# adc.net
KiCad netlist of a schematic drawn in Altium Designer
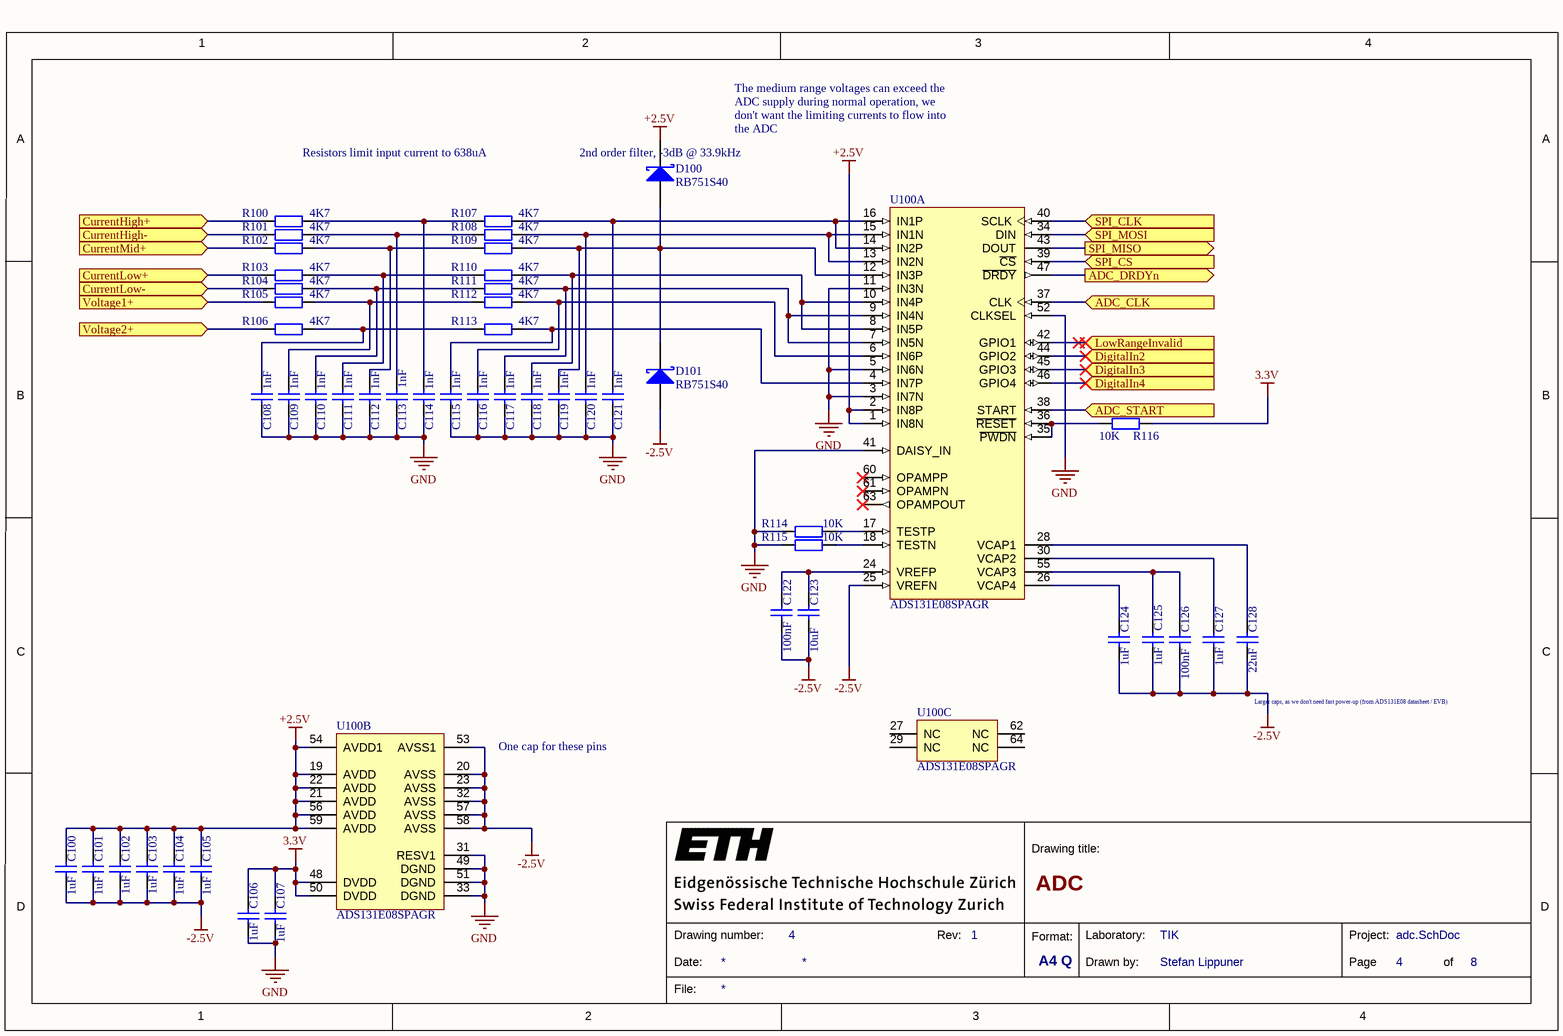
[diagram p0: adc.SchDoc]

(export (version "E")
  (design (tool "Eeschema 10.0.6"))
  (components
    (comp (ref "C100")
      (value "1uF")
      (footprint "CAPC0402(1005)60_L")
      (description "CAP 1uF 16V ±20% 0402 (1005 Metric) Thickness 0.6mm SMD")
      (fields (field (name "TOLERANCE") "Â±20%"))
      (libsource (lib "Altium Content Vault") (part "CMP-1034-02120"))
    )
    (comp (ref "C101")
      (value "1uF")
      (footprint "CAPC0402(1005)60_L")
      (description "CAP 1uF 16V ±20% 0402 (1005 Metric) Thickness 0.6mm SMD")
      (fields (field (name "TOLERANCE") "Â±20%"))
      (libsource (lib "Altium Content Vault") (part "CMP-1034-02120"))
    )
    (comp (ref "C102")
      (value "1uF")
      (footprint "CAPC0402(1005)60_L")
      (description "CAP 1uF 16V ±20% 0402 (1005 Metric) Thickness 0.6mm SMD")
      (fields (field (name "TOLERANCE") "Â±20%"))
      (libsource (lib "Altium Content Vault") (part "CMP-1034-02120"))
    )
    (comp (ref "C103")
      (value "1uF")
      (footprint "CAPC0402(1005)60_L")
      (description "CAP 1uF 16V ±20% 0402 (1005 Metric) Thickness 0.6mm SMD")
      (fields (field (name "TOLERANCE") "Â±20%"))
      (libsource (lib "Altium Content Vault") (part "CMP-1034-02120"))
    )
    (comp (ref "C104")
      (value "1uF")
      (footprint "CAPC0402(1005)60_L")
      (description "CAP 1uF 16V ±20% 0402 (1005 Metric) Thickness 0.6mm SMD")
      (fields (field (name "TOLERANCE") "Â±20%"))
      (libsource (lib "Altium Content Vault") (part "CMP-1034-02120"))
    )
    (comp (ref "C105")
      (value "1uF")
      (footprint "CAPC0402(1005)60_L")
      (description "CAP 1uF 16V ±20% 0402 (1005 Metric) Thickness 0.6mm SMD")
      (fields (field (name "TOLERANCE") "Â±20%"))
      (libsource (lib "Altium Content Vault") (part "CMP-1034-02120"))
    )
    (comp (ref "C106")
      (value "1uF")
      (footprint "CAPC0402(1005)60_L")
      (description "CAP 1uF 16V ±20% 0402 (1005 Metric) Thickness 0.6mm SMD")
      (fields (field (name "TOLERANCE") "Â±20%"))
      (libsource (lib "Altium Content Vault") (part "CMP-1034-02120"))
    )
    (comp (ref "C107")
      (value "1uF")
      (footprint "CAPC0402(1005)60_L")
      (description "CAP 1uF 16V ±20% 0402 (1005 Metric) Thickness 0.6mm SMD")
      (fields (field (name "TOLERANCE") "Â±20%"))
      (libsource (lib "Altium Content Vault") (part "CMP-1034-02120"))
    )
    (comp (ref "C108")
      (value "1nF")
      (footprint "CAPC0402(1005)60_L")
      (description "CAP 1nF 50V ±5% 0402 (1005 Metric) Thickness 0.6mm SMD")
      (fields (field (name "TOLERANCE") "Â±5%"))
      (libsource (lib "Altium Content Vault") (part "CAP"))
    )
    (comp (ref "C109")
      (value "1nF")
      (footprint "CAPC0402(1005)60_L")
      (description "CAP 1nF 50V ±5% 0402 (1005 Metric) Thickness 0.6mm SMD")
      (fields (field (name "TOLERANCE") "Â±5%"))
      (libsource (lib "Altium Content Vault") (part "CAP"))
    )
    (comp (ref "C110")
      (value "1nF")
      (footprint "CAPC0402(1005)60_L")
      (description "CAP 1nF 50V ±5% 0402 (1005 Metric) Thickness 0.6mm SMD")
      (fields (field (name "TOLERANCE") "Â±5%"))
      (libsource (lib "Altium Content Vault") (part "CAP"))
    )
    (comp (ref "C111")
      (value "1nF")
      (footprint "CAPC0402(1005)60_L")
      (description "CAP 1nF 50V ±5% 0402 (1005 Metric) Thickness 0.6mm SMD")
      (fields (field (name "TOLERANCE") "Â±5%"))
      (libsource (lib "Altium Content Vault") (part "CAP"))
    )
    (comp (ref "C112")
      (value "1nF")
      (footprint "CAPC0402(1005)60_L")
      (description "CAP 1nF 50V ±5% 0402 (1005 Metric) Thickness 0.6mm SMD")
      (fields (field (name "TOLERANCE") "Â±5%"))
      (libsource (lib "Altium Content Vault") (part "CAP"))
    )
    (comp (ref "C113")
      (value "1nF")
      (footprint "CAPC0402(1005)60_L")
      (description "CAP 1nF 50V ±5% 0402 (1005 Metric) Thickness 0.6mm SMD")
      (fields (field (name "TOLERANCE") "Â±5%"))
      (libsource (lib "Altium Content Vault") (part "CAP"))
    )
    (comp (ref "C114")
      (value "1nF")
      (footprint "CAPC0402(1005)60_L")
      (description "CAP 1nF 50V ±5% 0402 (1005 Metric) Thickness 0.6mm SMD")
      (fields (field (name "TOLERANCE") "Â±5%"))
      (libsource (lib "Altium Content Vault") (part "CAP"))
    )
    (comp (ref "C115")
      (value "1nF")
      (footprint "CAPC0402(1005)60_L")
      (description "CAP 1nF 50V ±5% 0402 (1005 Metric) Thickness 0.6mm SMD")
      (fields (field (name "TOLERANCE") "Â±5%"))
      (libsource (lib "Altium Content Vault") (part "CAP"))
    )
    (comp (ref "C116")
      (value "1nF")
      (footprint "CAPC0402(1005)60_L")
      (description "CAP 1nF 50V ±5% 0402 (1005 Metric) Thickness 0.6mm SMD")
      (fields (field (name "TOLERANCE") "Â±5%"))
      (libsource (lib "Altium Content Vault") (part "CAP"))
    )
    (comp (ref "C117")
      (value "1nF")
      (footprint "CAPC0402(1005)60_L")
      (description "CAP 1nF 50V ±5% 0402 (1005 Metric) Thickness 0.6mm SMD")
      (fields (field (name "TOLERANCE") "Â±5%"))
      (libsource (lib "Altium Content Vault") (part "CAP"))
    )
    (comp (ref "C118")
      (value "1nF")
      (footprint "CAPC0402(1005)60_L")
      (description "CAP 1nF 50V ±5% 0402 (1005 Metric) Thickness 0.6mm SMD")
      (fields (field (name "TOLERANCE") "Â±5%"))
      (libsource (lib "Altium Content Vault") (part "CAP"))
    )
    (comp (ref "C119")
      (value "1nF")
      (footprint "CAPC0402(1005)60_L")
      (description "CAP 1nF 50V ±5% 0402 (1005 Metric) Thickness 0.6mm SMD")
      (fields (field (name "TOLERANCE") "Â±5%"))
      (libsource (lib "Altium Content Vault") (part "CAP"))
    )
    (comp (ref "C120")
      (value "1nF")
      (footprint "CAPC0402(1005)60_L")
      (description "CAP 1nF 50V ±5% 0402 (1005 Metric) Thickness 0.6mm SMD")
      (fields (field (name "TOLERANCE") "Â±5%"))
      (libsource (lib "Altium Content Vault") (part "CAP"))
    )
    (comp (ref "C121")
      (value "1nF")
      (footprint "CAPC0402(1005)60_L")
      (description "CAP 1nF 50V ±5% 0402 (1005 Metric) Thickness 0.6mm SMD")
      (fields (field (name "TOLERANCE") "Â±5%"))
      (libsource (lib "Altium Content Vault") (part "CAP"))
    )
    (comp (ref "C122")
      (value "100nF")
      (footprint "CAPC0402(1005)60_L")
      (description "CAP 100nF 16V -20% to +80% 0402 (1005 Metric) Thickness 0.6mm SMD")
      (fields (field (name "TOLERANCE") "-20% to +80%"))
      (libsource (lib "Altium Content Vault") (part "CMP-1034-02071-1"))
    )
    (comp (ref "C123")
      (value "10uF")
      (footprint "CAPC0603(1608)100_L")
      (description "CAP 10uF 10V ±20% 0603 (1608 Metric) Thickness 1mm SMD")
      (fields (field (name "TOLERANCE") "Â±20%"))
      (libsource (lib "Altium Content Vault") (part "CMP-1035-02800-1"))
    )
    (comp (ref "C124")
      (value "1uF")
      (footprint "CAPC0402(1005)60_L")
      (description "CAP 1uF 16V ±20% 0402 (1005 Metric) Thickness 0.6mm SMD")
      (fields (field (name "TOLERANCE") "Â±20%"))
      (libsource (lib "Altium Content Vault") (part "CMP-1034-02120"))
    )
    (comp (ref "C125")
      (value "1uF")
      (footprint "CAPC0402(1005)60_L")
      (description "CAP 1uF 16V ±20% 0402 (1005 Metric) Thickness 0.6mm SMD")
      (fields (field (name "TOLERANCE") "Â±20%"))
      (libsource (lib "Altium Content Vault") (part "CMP-1034-02120"))
    )
    (comp (ref "C126")
      (value "100nF")
      (footprint "CAPC0402(1005)60_L")
      (description "CAP 100nF 16V -20% to +80% 0402 (1005 Metric) Thickness 0.6mm SMD")
      (fields (field (name "TOLERANCE") "-20% to +80%"))
      (libsource (lib "Altium Content Vault") (part "CMP-1034-02071-1"))
    )
    (comp (ref "C127")
      (value "1uF")
      (footprint "CAPC0402(1005)60_L")
      (description "CAP 1uF 16V ±20% 0402 (1005 Metric) Thickness 0.6mm SMD")
      (fields (field (name "TOLERANCE") "Â±20%"))
      (libsource (lib "Altium Content Vault") (part "CMP-1034-02120"))
    )
    (comp (ref "C128")
      (value "22uF")
      (footprint "CAPC0805(2012)145_L")
      (description "CAP 22uF 6.3V ±10% 0805 (2012 Metric) Thickness 1.45mm SMD")
      (fields (field (name "TOLERANCE") "Â±10%"))
      (libsource (lib "Altium Content Vault") (part "CAP"))
    )
    (comp (ref "D100")
      (value "RB751S40")
      (footprint "ONSC-SOD-523-2-502-01_V")
      (description "DIODE SCHOTTKY 40V 30MA SOD523F")
      (fields (field (name "MANUFACTURER") "Fairchild Semiconductor"))
      (libsource (lib "ETHZ Vault") (part "CMP-00225-2"))
    )
    (comp (ref "D101")
      (value "RB751S40")
      (footprint "ONSC-SOD-523-2-502-01_V")
      (description "DIODE SCHOTTKY 40V 30MA SOD523F")
      (fields (field (name "MANUFACTURER") "Fairchild Semiconductor"))
      (libsource (lib "ETHZ Vault") (part "Diode Schottky"))
    )
    (comp (ref "R100")
      (value "4K7")
      (footprint "RESC0402(1005)_L")
      (description "4K7 0.063W 1% 0402 (1005 Metric)  SMD")
      (fields (field (name "POWER") "0.063 W") (field (name "TOLERANCE") "1 %"))
      (libsource (lib "Altium Content Vault") (part "RES"))
    )
    (comp (ref "R101")
      (value "4K7")
      (footprint "RESC0402(1005)_L")
      (description "4K7 0.063W 1% 0402 (1005 Metric)  SMD")
      (fields (field (name "POWER") "0.063 W") (field (name "TOLERANCE") "1 %"))
      (libsource (lib "Altium Content Vault") (part "RES"))
    )
    (comp (ref "R102")
      (value "4K7")
      (footprint "RESC0402(1005)_L")
      (description "4K7 0.063W 1% 0402 (1005 Metric)  SMD")
      (fields (field (name "POWER") "0.063 W") (field (name "TOLERANCE") "1 %"))
      (libsource (lib "Altium Content Vault") (part "RES"))
    )
    (comp (ref "R103")
      (value "4K7")
      (footprint "RESC0402(1005)_L")
      (description "4K7 0.063W 1% 0402 (1005 Metric)  SMD")
      (fields (field (name "POWER") "0.063 W") (field (name "TOLERANCE") "1 %"))
      (libsource (lib "Altium Content Vault") (part "RES"))
    )
    (comp (ref "R104")
      (value "4K7")
      (footprint "RESC0402(1005)_L")
      (description "4K7 0.063W 1% 0402 (1005 Metric)  SMD")
      (fields (field (name "POWER") "0.063 W") (field (name "TOLERANCE") "1 %"))
      (libsource (lib "Altium Content Vault") (part "RES"))
    )
    (comp (ref "R105")
      (value "4K7")
      (footprint "RESC0402(1005)_L")
      (description "4K7 0.063W 1% 0402 (1005 Metric)  SMD")
      (fields (field (name "POWER") "0.063 W") (field (name "TOLERANCE") "1 %"))
      (libsource (lib "Altium Content Vault") (part "RES"))
    )
    (comp (ref "R106")
      (value "4K7")
      (footprint "RESC0402(1005)_L")
      (description "4K7 0.063W 1% 0402 (1005 Metric)  SMD")
      (fields (field (name "POWER") "0.063 W") (field (name "TOLERANCE") "1 %"))
      (libsource (lib "Altium Content Vault") (part "RES"))
    )
    (comp (ref "R107")
      (value "4K7")
      (footprint "RESC0402(1005)_L")
      (description "4K7 0.063W 1% 0402 (1005 Metric)  SMD")
      (fields (field (name "POWER") "0.063 W") (field (name "TOLERANCE") "1 %"))
      (libsource (lib "Altium Content Vault") (part "RES"))
    )
    (comp (ref "R108")
      (value "4K7")
      (footprint "RESC0402(1005)_L")
      (description "4K7 0.063W 1% 0402 (1005 Metric)  SMD")
      (fields (field (name "POWER") "0.063 W") (field (name "TOLERANCE") "1 %"))
      (libsource (lib "Altium Content Vault") (part "RES"))
    )
    (comp (ref "R109")
      (value "4K7")
      (footprint "RESC0402(1005)_L")
      (description "4K7 0.063W 1% 0402 (1005 Metric)  SMD")
      (fields (field (name "POWER") "0.063 W") (field (name "TOLERANCE") "1 %"))
      (libsource (lib "Altium Content Vault") (part "RES"))
    )
    (comp (ref "R110")
      (value "4K7")
      (footprint "RESC0402(1005)_L")
      (description "4K7 0.063W 1% 0402 (1005 Metric)  SMD")
      (fields (field (name "POWER") "0.063 W") (field (name "TOLERANCE") "1 %"))
      (libsource (lib "Altium Content Vault") (part "RES"))
    )
    (comp (ref "R111")
      (value "4K7")
      (footprint "RESC0402(1005)_L")
      (description "4K7 0.063W 1% 0402 (1005 Metric)  SMD")
      (fields (field (name "POWER") "0.063 W") (field (name "TOLERANCE") "1 %"))
      (libsource (lib "Altium Content Vault") (part "RES"))
    )
    (comp (ref "R112")
      (value "4K7")
      (footprint "RESC0402(1005)_L")
      (description "4K7 0.063W 1% 0402 (1005 Metric)  SMD")
      (fields (field (name "POWER") "0.063 W") (field (name "TOLERANCE") "1 %"))
      (libsource (lib "Altium Content Vault") (part "RES"))
    )
    (comp (ref "R113")
      (value "4K7")
      (footprint "RESC0402(1005)_L")
      (description "4K7 0.063W 1% 0402 (1005 Metric)  SMD")
      (fields (field (name "POWER") "0.063 W") (field (name "TOLERANCE") "1 %"))
      (libsource (lib "Altium Content Vault") (part "RES"))
    )
    (comp (ref "R114")
      (value "10K")
      (footprint "RESC0402(1005)_L")
      (description "10K 0.063W 1% 0402 (1005 Metric)  SMD")
      (fields (field (name "TOLERANCE") "1 %") (field (name "POWER") "0.063 W"))
      (libsource (lib "Altium Content Vault") (part "CMP-1011-00623-1"))
    )
    (comp (ref "R115")
      (value "10K")
      (footprint "RESC0402(1005)_L")
      (description "10K 0.063W 1% 0402 (1005 Metric)  SMD")
      (fields (field (name "TOLERANCE") "1 %") (field (name "POWER") "0.063 W"))
      (libsource (lib "Altium Content Vault") (part "CMP-1011-00623-1"))
    )
    (comp (ref "R116")
      (value "10K")
      (footprint "RESC0402(1005)_L")
      (description "10K 0.063W 1% 0402 (1005 Metric)  SMD")
      (fields (field (name "TOLERANCE") "1 %") (field (name "POWER") "0.063 W"))
      (libsource (lib "Altium Content Vault") (part "RES"))
    )
    (comp (ref "U100")
      (value "ADS131E08SPAGR")
      (footprint "QFP50P1000X1000X120_HS-64L")
      (description "Analog to Digital Converters - ADC 8-Channel, 24-Bit, AFE")
      (fields (field (name "MANUFACTURER") "Texas Instruments"))
      (libsource (lib "ETHZ Vault") (part "ADS131E08S"))
    )
  )
  (nets
    (net (code "1") (name "+2.5V") (class "Default")
      (node (ref "C100") (pin "2") (pinfunction "2_2") (pintype "passive"))
      (node (ref "C101") (pin "2") (pinfunction "2_2") (pintype "passive"))
      (node (ref "C102") (pin "2") (pinfunction "2_2") (pintype "passive"))
      (node (ref "C103") (pin "2") (pinfunction "2_2") (pintype "passive"))
      (node (ref "C104") (pin "2") (pinfunction "2_2") (pintype "passive"))
      (node (ref "C105") (pin "2") (pinfunction "2_2") (pintype "passive"))
      (node (ref "D100") (pin "1") (pinfunction "K_1") (pintype "passive"))
      (node (ref "U100") (pin "1") (pinfunction "IN8N_1") (pintype "input"))
      (node (ref "U100") (pin "19") (pinfunction "AVDD_19") (pintype "power_in"))
      (node (ref "U100") (pin "2") (pinfunction "IN8P_2") (pintype "input"))
      (node (ref "U100") (pin "21") (pinfunction "AVDD_21") (pintype "power_in"))
      (node (ref "U100") (pin "22") (pinfunction "AVDD_22") (pintype "power_in"))
      (node (ref "U100") (pin "54") (pinfunction "AVDD1_54") (pintype "power_in"))
      (node (ref "U100") (pin "56") (pinfunction "AVDD_56") (pintype "power_in"))
      (node (ref "U100") (pin "59") (pinfunction "AVDD_59") (pintype "power_in"))
    )
    (net (code "2") (name "-2.5V") (class "Default")
      (node (ref "C100") (pin "1") (pinfunction "1_1") (pintype "passive"))
      (node (ref "C101") (pin "1") (pinfunction "1_1") (pintype "passive"))
      (node (ref "C102") (pin "1") (pinfunction "1_1") (pintype "passive"))
      (node (ref "C103") (pin "1") (pinfunction "1_1") (pintype "passive"))
      (node (ref "C104") (pin "1") (pinfunction "1_1") (pintype "passive"))
      (node (ref "C105") (pin "1") (pinfunction "1_1") (pintype "passive"))
      (node (ref "C122") (pin "1") (pinfunction "1_1") (pintype "passive"))
      (node (ref "C123") (pin "1") (pinfunction "1_1") (pintype "passive"))
      (node (ref "C124") (pin "1") (pinfunction "1_1") (pintype "passive"))
      (node (ref "C125") (pin "1") (pinfunction "1_1") (pintype "passive"))
      (node (ref "C126") (pin "1") (pinfunction "1_1") (pintype "passive"))
      (node (ref "C127") (pin "1") (pinfunction "1_1") (pintype "passive"))
      (node (ref "C128") (pin "1") (pinfunction "1_1") (pintype "passive"))
      (node (ref "D101") (pin "2") (pinfunction "A_2") (pintype "passive"))
      (node (ref "U100") (pin "20") (pinfunction "AVSS_20") (pintype "power_in"))
      (node (ref "U100") (pin "23") (pinfunction "AVSS_23") (pintype "power_in"))
      (node (ref "U100") (pin "25") (pinfunction "VREFN_25") (pintype "input"))
      (node (ref "U100") (pin "32") (pinfunction "AVSS_32") (pintype "power_in"))
      (node (ref "U100") (pin "53") (pinfunction "AVSS1_53") (pintype "power_in"))
      (node (ref "U100") (pin "57") (pinfunction "AVSS_57") (pintype "power_in"))
      (node (ref "U100") (pin "58") (pinfunction "AVSS_58") (pintype "power_in"))
    )
    (net (code "3") (name "/ADC_CLK") (class "Default")
      (node (ref "U100") (pin "37") (pinfunction "CLK_37") (pintype "input"))
    )
    (net (code "4") (name "/ADC_DRDYn") (class "Default")
      (node (ref "U100") (pin "47") (pinfunction "~{DRDY}_47") (pintype "output"))
    )
    (net (code "5") (name "/ADC_START") (class "Default")
      (node (ref "U100") (pin "38") (pinfunction "START_38") (pintype "input"))
    )
    (net (code "6") (name "/CurrentHigh+") (class "Default")
      (node (ref "R100") (pin "2") (pinfunction "2_2") (pintype "passive"))
    )
    (net (code "7") (name "/CurrentHigh-") (class "Default")
      (node (ref "R101") (pin "2") (pinfunction "2_2") (pintype "passive"))
    )
    (net (code "8") (name "/CurrentLow+") (class "Default")
      (node (ref "R103") (pin "2") (pinfunction "2_2") (pintype "passive"))
    )
    (net (code "9") (name "/CurrentLow-") (class "Default")
      (node (ref "R104") (pin "2") (pinfunction "2_2") (pintype "passive"))
    )
    (net (code "10") (name "/CurrentMid+") (class "Default")
      (node (ref "R102") (pin "2") (pinfunction "2_2") (pintype "passive"))
    )
    (net (code "11") (name "/DigitalIn2") (class "Default")
      (node (ref "U100") (pin "44") (pinfunction "GPIO2_44") (pintype "bidirectional+no_connect"))
    )
    (net (code "12") (name "/DigitalIn3") (class "Default")
      (node (ref "U100") (pin "45") (pinfunction "GPIO3_45") (pintype "bidirectional+no_connect"))
    )
    (net (code "13") (name "/DigitalIn4") (class "Default")
      (node (ref "U100") (pin "46") (pinfunction "GPIO4_46") (pintype "bidirectional+no_connect"))
    )
    (net (code "14") (name "/LowRangeInvalid") (class "Default")
      (node (ref "U100") (pin "42") (pinfunction "GPIO1_42") (pintype "bidirectional+no_connect"))
    )
    (net (code "15") (name "/SPI_CLK") (class "Default")
      (node (ref "U100") (pin "40") (pinfunction "SCLK_40") (pintype "input"))
    )
    (net (code "16") (name "/SPI_CS") (class "Default")
      (node (ref "U100") (pin "39") (pinfunction "~{CS}_39") (pintype "input"))
    )
    (net (code "17") (name "/SPI_MISO") (class "Default")
      (node (ref "U100") (pin "43") (pinfunction "DOUT_43") (pintype "tri_state"))
    )
    (net (code "18") (name "/SPI_MOSI") (class "Default")
      (node (ref "U100") (pin "34") (pinfunction "DIN_34") (pintype "input"))
    )
    (net (code "19") (name "/Voltage1+") (class "Default")
      (node (ref "R105") (pin "2") (pinfunction "2_2") (pintype "passive"))
    )
    (net (code "20") (name "/Voltage2+") (class "Default")
      (node (ref "R106") (pin "2") (pinfunction "2_2") (pintype "passive"))
    )
    (net (code "21") (name "3.3V") (class "Default")
      (node (ref "C106") (pin "2") (pinfunction "2_2") (pintype "passive"))
      (node (ref "C107") (pin "2") (pinfunction "2_2") (pintype "passive"))
      (node (ref "R116") (pin "1") (pinfunction "1_1") (pintype "passive"))
      (node (ref "U100") (pin "48") (pinfunction "DVDD_48") (pintype "power_in"))
      (node (ref "U100") (pin "50") (pinfunction "DVDD_50") (pintype "power_in"))
    )
    (net (code "22") (name "GND") (class "Default")
      (node (ref "C106") (pin "1") (pinfunction "1_1") (pintype "passive"))
      (node (ref "C107") (pin "1") (pinfunction "1_1") (pintype "passive"))
      (node (ref "C108") (pin "1") (pinfunction "1_1") (pintype "passive"))
      (node (ref "C109") (pin "1") (pinfunction "1_1") (pintype "passive"))
      (node (ref "C110") (pin "1") (pinfunction "1_1") (pintype "passive"))
      (node (ref "C111") (pin "1") (pinfunction "1_1") (pintype "passive"))
      (node (ref "C112") (pin "1") (pinfunction "1_1") (pintype "passive"))
      (node (ref "C113") (pin "1") (pinfunction "1_1") (pintype "passive"))
      (node (ref "C114") (pin "1") (pinfunction "1_1") (pintype "passive"))
      (node (ref "C115") (pin "1") (pinfunction "1_1") (pintype "passive"))
      (node (ref "C116") (pin "1") (pinfunction "1_1") (pintype "passive"))
      (node (ref "C117") (pin "1") (pinfunction "1_1") (pintype "passive"))
      (node (ref "C118") (pin "1") (pinfunction "1_1") (pintype "passive"))
      (node (ref "C119") (pin "1") (pinfunction "1_1") (pintype "passive"))
      (node (ref "C120") (pin "1") (pinfunction "1_1") (pintype "passive"))
      (node (ref "C121") (pin "1") (pinfunction "1_1") (pintype "passive"))
      (node (ref "R114") (pin "1") (pinfunction "1_1") (pintype "passive"))
      (node (ref "R115") (pin "1") (pinfunction "1_1") (pintype "passive"))
      (node (ref "U100") (pin "11") (pinfunction "IN3N_11") (pintype "input"))
      (node (ref "U100") (pin "3") (pinfunction "IN7N_3") (pintype "input"))
      (node (ref "U100") (pin "31") (pinfunction "RESV1_31") (pintype "power_in"))
      (node (ref "U100") (pin "33") (pinfunction "DGND_33") (pintype "power_in"))
      (node (ref "U100") (pin "41") (pinfunction "DAISY_IN_41") (pintype "input"))
      (node (ref "U100") (pin "49") (pinfunction "DGND_49") (pintype "power_in"))
      (node (ref "U100") (pin "5") (pinfunction "IN6N_5") (pintype "input"))
      (node (ref "U100") (pin "51") (pinfunction "DGND_51") (pintype "power_in"))
      (node (ref "U100") (pin "52") (pinfunction "CLKSEL_52") (pintype "input"))
    )
    (net (code "23") (name "Net-(C108-Pad2)") (class "Default")
      (node (ref "C108") (pin "2") (pinfunction "2_2") (pintype "passive"))
      (node (ref "R106") (pin "1") (pinfunction "1_1") (pintype "passive"))
      (node (ref "R113") (pin "2") (pinfunction "2_2") (pintype "passive"))
    )
    (net (code "24") (name "Net-(C109-Pad2)") (class "Default")
      (node (ref "C109") (pin "2") (pinfunction "2_2") (pintype "passive"))
      (node (ref "R105") (pin "1") (pinfunction "1_1") (pintype "passive"))
      (node (ref "R112") (pin "2") (pinfunction "2_2") (pintype "passive"))
    )
    (net (code "25") (name "Net-(C110-Pad2)") (class "Default")
      (node (ref "C110") (pin "2") (pinfunction "2_2") (pintype "passive"))
      (node (ref "R104") (pin "1") (pinfunction "1_1") (pintype "passive"))
      (node (ref "R111") (pin "2") (pinfunction "2_2") (pintype "passive"))
    )
    (net (code "26") (name "Net-(C111-Pad2)") (class "Default")
      (node (ref "C111") (pin "2") (pinfunction "2_2") (pintype "passive"))
      (node (ref "R103") (pin "1") (pinfunction "1_1") (pintype "passive"))
      (node (ref "R110") (pin "2") (pinfunction "2_2") (pintype "passive"))
    )
    (net (code "27") (name "Net-(C112-Pad2)") (class "Default")
      (node (ref "C112") (pin "2") (pinfunction "2_2") (pintype "passive"))
      (node (ref "R102") (pin "1") (pinfunction "1_1") (pintype "passive"))
      (node (ref "R109") (pin "2") (pinfunction "2_2") (pintype "passive"))
    )
    (net (code "28") (name "Net-(C113-Pad2)") (class "Default")
      (node (ref "C113") (pin "2") (pinfunction "2_2") (pintype "passive"))
      (node (ref "R101") (pin "1") (pinfunction "1_1") (pintype "passive"))
      (node (ref "R108") (pin "2") (pinfunction "2_2") (pintype "passive"))
    )
    (net (code "29") (name "Net-(C114-Pad2)") (class "Default")
      (node (ref "C114") (pin "2") (pinfunction "2_2") (pintype "passive"))
      (node (ref "R100") (pin "1") (pinfunction "1_1") (pintype "passive"))
      (node (ref "R107") (pin "2") (pinfunction "2_2") (pintype "passive"))
    )
    (net (code "30") (name "Net-(D100-A)") (class "Default")
      (node (ref "C119") (pin "2") (pinfunction "2_2") (pintype "passive"))
      (node (ref "D100") (pin "2") (pinfunction "A_2") (pintype "passive"))
      (node (ref "D101") (pin "1") (pinfunction "K_1") (pintype "passive"))
      (node (ref "R109") (pin "1") (pinfunction "1_1") (pintype "passive"))
      (node (ref "U100") (pin "12") (pinfunction "IN3P_12") (pintype "input"))
    )
    (net (code "31") (name "Net-(U100A-IN1N)") (class "Default")
      (node (ref "C120") (pin "2") (pinfunction "2_2") (pintype "passive"))
      (node (ref "R108") (pin "1") (pinfunction "1_1") (pintype "passive"))
      (node (ref "U100") (pin "13") (pinfunction "IN2N_13") (pintype "input"))
      (node (ref "U100") (pin "15") (pinfunction "IN1N_15") (pintype "input"))
    )
    (net (code "32") (name "Net-(U100A-IN1P)") (class "Default")
      (node (ref "C121") (pin "2") (pinfunction "2_2") (pintype "passive"))
      (node (ref "R107") (pin "1") (pinfunction "1_1") (pintype "passive"))
      (node (ref "U100") (pin "14") (pinfunction "IN2P_14") (pintype "input"))
      (node (ref "U100") (pin "16") (pinfunction "IN1P_16") (pintype "input"))
    )
    (net (code "33") (name "Net-(U100A-IN4N)") (class "Default")
      (node (ref "C117") (pin "2") (pinfunction "2_2") (pintype "passive"))
      (node (ref "R111") (pin "1") (pinfunction "1_1") (pintype "passive"))
      (node (ref "U100") (pin "7") (pinfunction "IN5N_7") (pintype "input"))
      (node (ref "U100") (pin "9") (pinfunction "IN4N_9") (pintype "input"))
    )
    (net (code "34") (name "Net-(U100A-IN4P)") (class "Default")
      (node (ref "C118") (pin "2") (pinfunction "2_2") (pintype "passive"))
      (node (ref "R110") (pin "1") (pinfunction "1_1") (pintype "passive"))
      (node (ref "U100") (pin "10") (pinfunction "IN4P_10") (pintype "input"))
      (node (ref "U100") (pin "8") (pinfunction "IN5P_8") (pintype "input"))
    )
    (net (code "35") (name "Net-(U100A-IN6P)") (class "Default")
      (node (ref "C116") (pin "2") (pinfunction "2_2") (pintype "passive"))
      (node (ref "R112") (pin "1") (pinfunction "1_1") (pintype "passive"))
      (node (ref "U100") (pin "6") (pinfunction "IN6P_6") (pintype "input"))
    )
    (net (code "36") (name "Net-(U100A-IN7P)") (class "Default")
      (node (ref "C115") (pin "2") (pinfunction "2_2") (pintype "passive"))
      (node (ref "R113") (pin "1") (pinfunction "1_1") (pintype "passive"))
      (node (ref "U100") (pin "4") (pinfunction "IN7P_4") (pintype "input"))
    )
    (net (code "37") (name "Net-(U100A-TESTN)") (class "Default")
      (node (ref "R115") (pin "2") (pinfunction "2_2") (pintype "passive"))
      (node (ref "U100") (pin "18") (pinfunction "TESTN_18") (pintype "input"))
    )
    (net (code "38") (name "Net-(U100A-TESTP)") (class "Default")
      (node (ref "R114") (pin "2") (pinfunction "2_2") (pintype "passive"))
      (node (ref "U100") (pin "17") (pinfunction "TESTP_17") (pintype "input"))
    )
    (net (code "39") (name "Net-(U100A-VCAP1)") (class "Default")
      (node (ref "C128") (pin "2") (pinfunction "2_2") (pintype "passive"))
      (node (ref "U100") (pin "28") (pinfunction "VCAP1_28") (pintype "passive"))
    )
    (net (code "40") (name "Net-(U100A-VCAP2)") (class "Default")
      (node (ref "C127") (pin "2") (pinfunction "2_2") (pintype "passive"))
      (node (ref "U100") (pin "30") (pinfunction "VCAP2_30") (pintype "passive"))
    )
    (net (code "41") (name "Net-(U100A-VCAP3)") (class "Default")
      (node (ref "C125") (pin "2") (pinfunction "2_2") (pintype "passive"))
      (node (ref "C126") (pin "2") (pinfunction "2_2") (pintype "passive"))
      (node (ref "U100") (pin "55") (pinfunction "VCAP3_55") (pintype "passive"))
    )
    (net (code "42") (name "Net-(U100A-VCAP4)") (class "Default")
      (node (ref "C124") (pin "2") (pinfunction "2_2") (pintype "passive"))
      (node (ref "U100") (pin "26") (pinfunction "VCAP4_26") (pintype "passive"))
    )
    (net (code "43") (name "Net-(U100A-VREFP)") (class "Default")
      (node (ref "C122") (pin "2") (pinfunction "2_2") (pintype "passive"))
      (node (ref "C123") (pin "2") (pinfunction "2_2") (pintype "passive"))
      (node (ref "U100") (pin "24") (pinfunction "VREFP_24") (pintype "input"))
    )
    (net (code "44") (name "Net-(U100A-~{PWDN})") (class "Default")
      (node (ref "R116") (pin "2") (pinfunction "2_2") (pintype "passive"))
      (node (ref "U100") (pin "35") (pinfunction "~{PWDN}_35") (pintype "input"))
      (node (ref "U100") (pin "36") (pinfunction "~{RESET}_36") (pintype "input"))
    )
    (net (code "45") (name "unconnected-(U100A-OPAMPN-Pad61)") (class "Default")
      (node (ref "U100") (pin "61") (pinfunction "OPAMPN_61") (pintype "input+no_connect"))
    )
    (net (code "46") (name "unconnected-(U100A-OPAMPOUT-Pad63)") (class "Default")
      (node (ref "U100") (pin "63") (pinfunction "OPAMPOUT_63") (pintype "output+no_connect"))
    )
    (net (code "47") (name "unconnected-(U100A-OPAMPP-Pad60)") (class "Default")
      (node (ref "U100") (pin "60") (pinfunction "OPAMPP_60") (pintype "input+no_connect"))
    )
    (net (code "48") (name "unconnected-(U100C-NC-Pad27)") (class "Default")
      (node (ref "U100") (pin "27") (pinfunction "NC_27") (pintype "passive"))
    )
    (net (code "49") (name "unconnected-(U100C-NC-Pad29)") (class "Default")
      (node (ref "U100") (pin "29") (pinfunction "NC_29") (pintype "passive"))
    )
    (net (code "50") (name "unconnected-(U100C-NC-Pad62)") (class "Default")
      (node (ref "U100") (pin "62") (pinfunction "NC_62") (pintype "passive"))
    )
    (net (code "51") (name "unconnected-(U100C-NC-Pad64)") (class "Default")
      (node (ref "U100") (pin "64") (pinfunction "NC_64") (pintype "passive"))
    )
  )
)
